# RainbowClock.net
KiCad netlist of a schematic drawn in Altium Designer
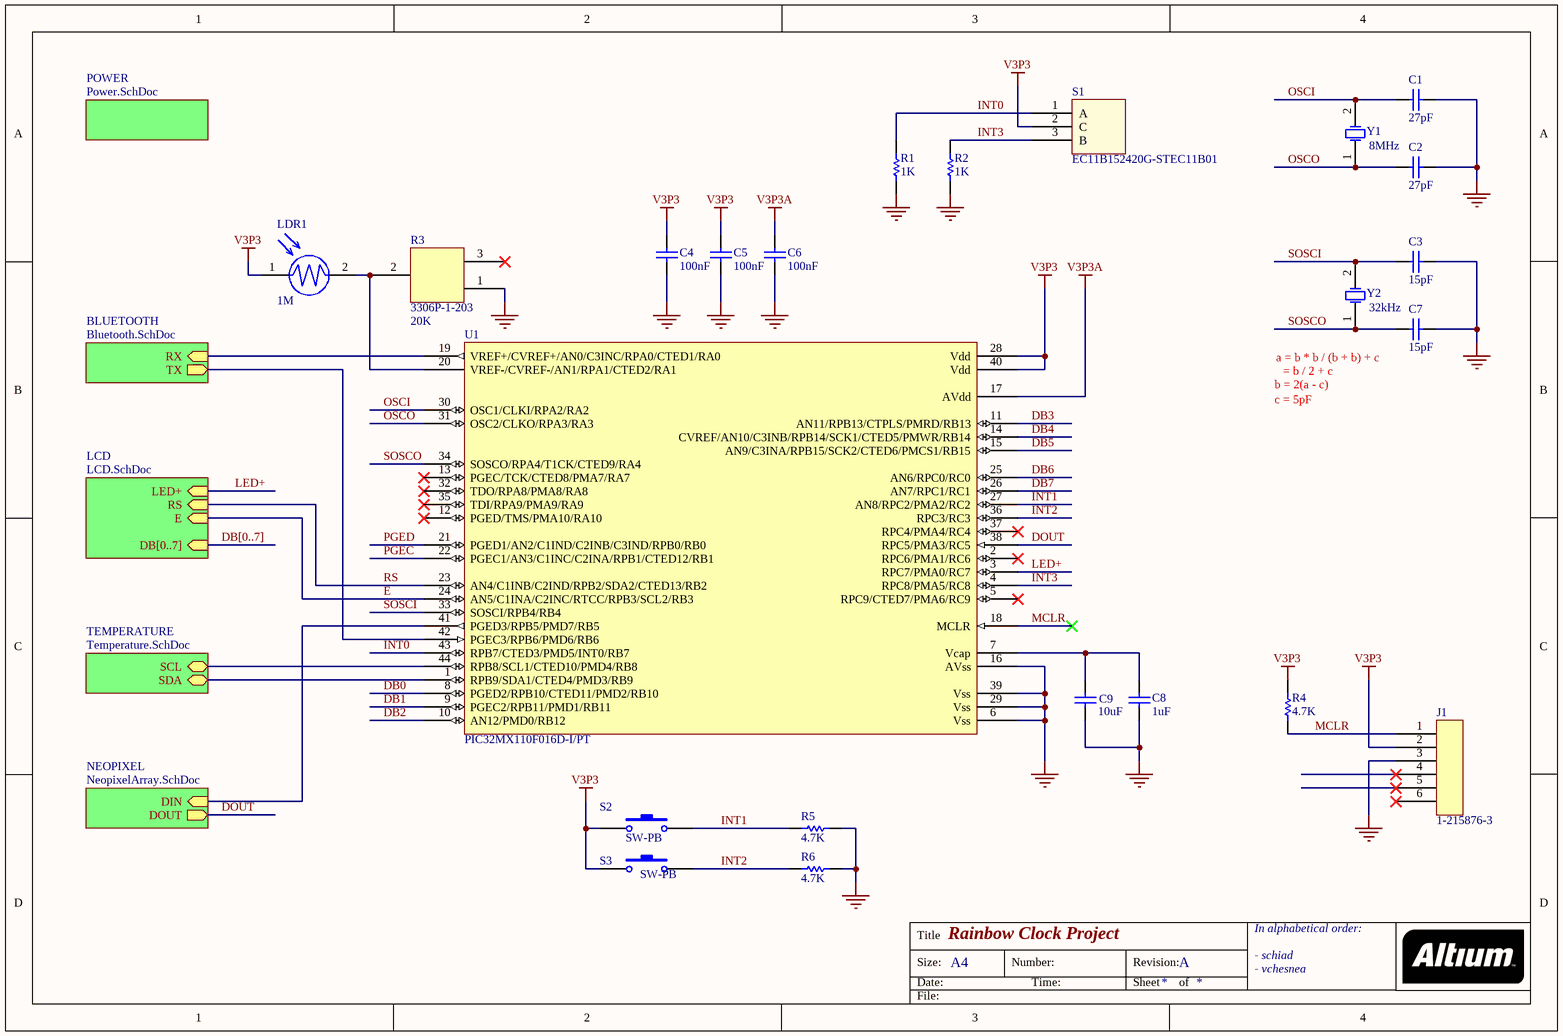
[diagram p0: RainbowClock.SchDoc]

(export (version "E")
  (design (tool "Eeschema 10.0.6"))
  (components
    (comp (ref "C1")
      (value "27pF")
      (footprint "CAP0603")
      (description "Capacitor")
      (libsource (lib "Miscellaneous Devices") (part "Cap"))
    )
    (comp (ref "C2")
      (value "27pF")
      (footprint "CAP0603")
      (description "Capacitor")
      (libsource (lib "Miscellaneous Devices") (part "Cap"))
    )
    (comp (ref "C3")
      (value "15pF")
      (footprint "CAP0603")
      (description "Capacitor")
      (libsource (lib "Miscellaneous Devices") (part "Cap"))
    )
    (comp (ref "C4")
      (value "100nF")
      (footprint "CAP0603")
      (description "Capacitor")
      (libsource (lib "Miscellaneous Devices") (part "Cap"))
    )
    (comp (ref "C5")
      (value "100nF")
      (footprint "CAP0603")
      (description "Capacitor")
      (libsource (lib "Miscellaneous Devices") (part "Cap"))
    )
    (comp (ref "C6")
      (value "100nF")
      (footprint "CAP0603")
      (description "Capacitor")
      (libsource (lib "Miscellaneous Devices") (part "Cap"))
    )
    (comp (ref "C7")
      (value "15pF")
      (footprint "CAP0603")
      (description "Capacitor")
      (libsource (lib "Miscellaneous Devices") (part "Cap"))
    )
    (comp (ref "C8")
      (value "1uF")
      (footprint "CAP0603")
      (description "Capacitor")
      (libsource (lib "Miscellaneous Devices") (part "Cap"))
    )
    (comp (ref "C9")
      (value "10uF")
      (footprint "CAP0603")
      (description "Capacitor")
      (libsource (lib "Miscellaneous Devices") (part "Cap"))
    )
    (comp (ref "J1")
      (value "1-215876-3")
      (description "Tyco 1-215876-3")
      (libsource (lib "Components") (part "1-215876-3"))
    )
    (comp (ref "LDR1")
      (value "1M")
      (footprint "VT935G")
      (description "Photoresistor")
      (fields (field (name "Comment") "LDR"))
      (libsource (lib "Components") (part "LDR"))
    )
    (comp (ref "R1")
      (value "1K")
      (footprint "RES0603")
      (description "Resistor")
      (libsource (lib "Miscellaneous Devices") (part "Res1"))
    )
    (comp (ref "R2")
      (value "1K")
      (footprint "RES0603")
      (description "Resistor")
      (libsource (lib "Miscellaneous Devices") (part "Res1"))
    )
    (comp (ref "R3")
      (value "3306P-1-203")
      (footprint "3306P-1-202")
      (description "Trimpot")
      (fields (field (name "ALTIUM_VALUE") "20K"))
      (libsource (lib "Components") (part "3306P-1-202"))
    )
    (comp (ref "R4")
      (value "4.7K")
      (footprint "RES0603")
      (description "Resistor")
      (libsource (lib "Miscellaneous Devices") (part "Res1"))
    )
    (comp (ref "R5")
      (value "4.7K")
      (footprint "RES0603")
      (description "Resistor")
      (libsource (lib "Miscellaneous Devices") (part "Res1"))
    )
    (comp (ref "R6")
      (value "4.7K")
      (footprint "RES0603")
      (description "Resistor")
      (libsource (lib "Miscellaneous Devices") (part "Res1"))
    )
    (comp (ref "S1")
      (value "EC11B152420G-STEC11B01")
      (footprint "EC11B152420G-STEC11B01")
      (description "Rotary encoder")
      (libsource (lib "Components") (part "EC11B152420G-STEC11B01"))
    )
    (comp (ref "S2")
      (value "SW-PB")
      (footprint "1-1825027-4")
      (description "Switch")
      (libsource (lib "Miscellaneous Devices") (part "SW-PB"))
    )
    (comp (ref "S3")
      (value "SW-PB")
      (footprint "1-1825027-4")
      (description "Switch")
      (libsource (lib "Miscellaneous Devices") (part "SW-PB"))
    )
    (comp (ref "U1")
      (value "PIC32MX110F016D-I/PT")
      (footprint "PIC32MX110F016H-I/PT")
      (description "Microcontroller")
      (libsource (lib "Components") (part "PIC32MX110F016D-I/PT"))
    )
    (comp (ref "Y1")
      (value "8MHz")
      (footprint "FOXSLF/080-20")
      (description "Crystal Oscillator")
      (fields (field (name "Comment") "8MHz XTAL"))
      (libsource (lib "Miscellaneous Devices") (part "XTAL"))
    )
    (comp (ref "Y2")
      (value "32kHz")
      (footprint "NCL38LF")
      (description "Crystal Oscillator")
      (fields (field (name "Comment") "32kHz XTAL"))
      (libsource (lib "Miscellaneous Devices") (part "XTAL"))
    )
  )
  (nets
    (net (code "1") (name "/DB0") (class "Default")
      (node (ref "U1") (pin "8") (pinfunction "PGED2/RPB10/CTED11/PMD2/RB10_8") (pintype "bidirectional"))
    )
    (net (code "2") (name "/DB1") (class "Default")
      (node (ref "U1") (pin "9") (pinfunction "PGEC2/RPB11/PMD1/RB11_9") (pintype "bidirectional"))
    )
    (net (code "3") (name "/DB2") (class "Default")
      (node (ref "U1") (pin "10") (pinfunction "AN12/PMD0/RB12_10") (pintype "bidirectional"))
    )
    (net (code "4") (name "/DB3") (class "Default")
      (node (ref "U1") (pin "11") (pinfunction "AN11/RPB13/CTPLS/PMRD/RB13_11") (pintype "bidirectional"))
    )
    (net (code "5") (name "/DB4") (class "Default")
      (node (ref "U1") (pin "14") (pinfunction "CVREF/AN10/C3INB/RPB14/SCK1/CTED5/PMWR/RB14_14") (pintype "bidirectional"))
    )
    (net (code "6") (name "/DB5") (class "Default")
      (node (ref "U1") (pin "15") (pinfunction "AN9/C3INA/RPB15/SCK2/CTED6/PMCS1/RB15_15") (pintype "bidirectional"))
    )
    (net (code "7") (name "/DB6") (class "Default")
      (node (ref "U1") (pin "25") (pinfunction "AN6/RPC0/RC0_25") (pintype "bidirectional"))
    )
    (net (code "8") (name "/DB7") (class "Default")
      (node (ref "U1") (pin "26") (pinfunction "AN7/RPC1/RC1_26") (pintype "bidirectional"))
    )
    (net (code "10") (name "/DIN") (class "Default")
      (node (ref "U1") (pin "41") (pinfunction "PGED3/RPB5/PMD7/RB5_41") (pintype "output"))
    )
    (net (code "11") (name "/DOUT") (class "Default")
      (node (ref "U1") (pin "38") (pinfunction "RPC5/PMA3/RC5_38") (pintype "input"))
    )
    (net (code "12") (name "/E") (class "Default")
      (node (ref "U1") (pin "24") (pinfunction "AN5/C1INA/C2INC/RTCC/RPB3/SCL2/RB3_24") (pintype "bidirectional"))
    )
    (net (code "13") (name "/INT0") (class "Default")
      (node (ref "R1") (pin "1") (pinfunction "1_1") (pintype "passive"))
      (node (ref "S1") (pin "1") (pinfunction "A_1") (pintype "passive"))
      (node (ref "U1") (pin "43") (pinfunction "RPB7/CTED3/PMD5/INT0/RB7_43") (pintype "bidirectional"))
    )
    (net (code "14") (name "/INT1") (class "Default")
      (node (ref "R5") (pin "2") (pinfunction "2_2") (pintype "passive"))
      (node (ref "S2") (pin "2") (pinfunction "2_2") (pintype "passive"))
      (node (ref "U1") (pin "27") (pinfunction "AN8/RPC2/PMA2/RC2_27") (pintype "bidirectional"))
    )
    (net (code "15") (name "/INT2") (class "Default")
      (node (ref "R6") (pin "2") (pinfunction "2_2") (pintype "passive"))
      (node (ref "S3") (pin "2") (pinfunction "2_2") (pintype "passive"))
      (node (ref "U1") (pin "36") (pinfunction "RPC3/RC3_36") (pintype "bidirectional"))
    )
    (net (code "16") (name "/INT3") (class "Default")
      (node (ref "R2") (pin "2") (pinfunction "2_2") (pintype "passive"))
      (node (ref "S1") (pin "3") (pinfunction "B_3") (pintype "passive"))
      (node (ref "U1") (pin "4") (pinfunction "RPC8/PMA5/RC8_4") (pintype "bidirectional"))
    )
    (net (code "17") (name "/LED+") (class "Default")
      (node (ref "U1") (pin "3") (pinfunction "RPC7/PMA0/RC7_3") (pintype "bidirectional"))
    )
    (net (code "18") (name "/MCLR") (class "Default")
      (node (ref "J1") (pin "1") (pintype "passive"))
      (node (ref "R4") (pin "1") (pinfunction "1_1") (pintype "passive"))
      (node (ref "U1") (pin "18") (pinfunction "MCLR_18") (pintype "input"))
    )
    (net (code "19") (name "/OSCI") (class "Default")
      (node (ref "C1") (pin "1") (pinfunction "1_1") (pintype "passive"))
      (node (ref "U1") (pin "30") (pinfunction "OSC1/CLKI/RPA2/RA2_30") (pintype "bidirectional"))
      (node (ref "Y1") (pin "2") (pinfunction "OSC2_2") (pintype "passive"))
    )
    (net (code "20") (name "/OSCO") (class "Default")
      (node (ref "C2") (pin "1") (pinfunction "1_1") (pintype "passive"))
      (node (ref "U1") (pin "31") (pinfunction "OSC2/CLKO/RPA3/RA3_31") (pintype "bidirectional"))
      (node (ref "Y1") (pin "1") (pinfunction "OSC1_1") (pintype "passive"))
    )
    (net (code "21") (name "/PGEC") (class "Default")
      (node (ref "U1") (pin "22") (pinfunction "PGEC1/AN3/C1INC/C2INA/RPB1/CTED12/RB1_22") (pintype "bidirectional"))
    )
    (net (code "22") (name "/PGED") (class "Default")
      (node (ref "U1") (pin "21") (pinfunction "PGED1/AN2/C1IND/C2INB/C3IND/RPB0/RB0_21") (pintype "bidirectional"))
    )
    (net (code "23") (name "/RS") (class "Default")
      (node (ref "U1") (pin "23") (pinfunction "AN4/C1INB/C2IND/RPB2/SDA2/CTED13/RB2_23") (pintype "bidirectional"))
    )
    (net (code "24") (name "/RX") (class "Default")
      (node (ref "U1") (pin "19") (pinfunction "VREF+/CVREF+/AN0/C3INC/RPA0/CTED1/RA0_19") (pintype "output"))
    )
    (net (code "25") (name "/SCL") (class "Default")
      (node (ref "U1") (pin "44") (pinfunction "RPB8/SCL1/CTED10/PMD4/RB8_44") (pintype "bidirectional"))
    )
    (net (code "26") (name "/SDA") (class "Default")
      (node (ref "U1") (pin "1") (pinfunction "RPB9/SDA1/CTED4/PMD3/RB9_1") (pintype "bidirectional"))
    )
    (net (code "27") (name "/SOSCI") (class "Default")
      (node (ref "C3") (pin "1") (pinfunction "1_1") (pintype "passive"))
      (node (ref "U1") (pin "33") (pinfunction "SOSCI/RPB4/RB4_33") (pintype "bidirectional"))
      (node (ref "Y2") (pin "2") (pinfunction "OSC2_2") (pintype "passive"))
    )
    (net (code "28") (name "/SOSCO") (class "Default")
      (node (ref "C7") (pin "1") (pinfunction "1_1") (pintype "passive"))
      (node (ref "U1") (pin "34") (pinfunction "SOSCO/RPA4/T1CK/CTED9/RA4_34") (pintype "bidirectional"))
      (node (ref "Y2") (pin "1") (pinfunction "OSC1_1") (pintype "passive"))
    )
    (net (code "29") (name "/TX") (class "Default")
      (node (ref "U1") (pin "42") (pinfunction "PGEC3/RPB6/PMD6/RB6_42") (pintype "input"))
    )
    (net (code "30") (name "GND") (class "Default")
      (node (ref "C1") (pin "2") (pinfunction "2_2") (pintype "passive"))
      (node (ref "C2") (pin "2") (pinfunction "2_2") (pintype "passive"))
      (node (ref "C3") (pin "2") (pinfunction "2_2") (pintype "passive"))
      (node (ref "C4") (pin "1") (pinfunction "1_1") (pintype "passive"))
      (node (ref "C5") (pin "1") (pinfunction "1_1") (pintype "passive"))
      (node (ref "C6") (pin "1") (pinfunction "1_1") (pintype "passive"))
      (node (ref "C7") (pin "2") (pinfunction "2_2") (pintype "passive"))
      (node (ref "J1") (pin "3") (pintype "passive"))
      (node (ref "R1") (pin "2") (pinfunction "2_2") (pintype "passive"))
      (node (ref "R2") (pin "1") (pinfunction "1_1") (pintype "passive"))
      (node (ref "R3") (pin "1") (pinfunction "1_1") (pintype "power_in"))
      (node (ref "R5") (pin "1") (pinfunction "1_1") (pintype "passive"))
      (node (ref "R6") (pin "1") (pinfunction "1_1") (pintype "passive"))
    )
    (net (code "31") (name "Net-(U1-VREF-{slash}CVREF-{slash}AN1{slash}RPA1{slash}CTED2{slash}RA1)") (class "Default")
      (node (ref "LDR1") (pin "2") (pinfunction "2_2") (pintype "power_in"))
      (node (ref "R3") (pin "2") (pinfunction "2_2") (pintype "power_in"))
      (node (ref "U1") (pin "20") (pinfunction "VREF-/CVREF-/AN1/RPA1/CTED2/RA1_20") (pintype "passive"))
    )
    (net (code "32") (name "Net-(U1-Vcap)") (class "Default")
      (node (ref "C8") (pin "2") (pinfunction "2_2") (pintype "passive"))
      (node (ref "C9") (pin "2") (pinfunction "2_2") (pintype "passive"))
      (node (ref "U1") (pin "7") (pinfunction "Vcap_7") (pintype "power_in"))
    )
    (net (code "33") (name "V3P3") (class "Default")
      (node (ref "C4") (pin "2") (pinfunction "2_2") (pintype "passive"))
      (node (ref "C5") (pin "2") (pinfunction "2_2") (pintype "passive"))
      (node (ref "J1") (pin "2") (pintype "passive"))
      (node (ref "LDR1") (pin "1") (pinfunction "1_1") (pintype "power_in"))
      (node (ref "R4") (pin "2") (pinfunction "2_2") (pintype "passive"))
      (node (ref "S1") (pin "2") (pinfunction "C_2") (pintype "passive"))
      (node (ref "S2") (pin "1") (pinfunction "1_1") (pintype "passive"))
      (node (ref "S3") (pin "1") (pinfunction "1_1") (pintype "passive"))
      (node (ref "U1") (pin "28") (pinfunction "Vdd_28") (pintype "power_in"))
      (node (ref "U1") (pin "40") (pinfunction "Vdd_40") (pintype "power_in"))
    )
    (net (code "34") (name "V3P3A") (class "Default")
      (node (ref "C6") (pin "2") (pinfunction "2_2") (pintype "passive"))
      (node (ref "U1") (pin "17") (pinfunction "AVdd_17") (pintype "power_in"))
    )
    (net (code "35") (name "VSS") (class "Default")
      (node (ref "C8") (pin "1") (pinfunction "1_1") (pintype "passive"))
      (node (ref "C9") (pin "1") (pinfunction "1_1") (pintype "passive"))
      (node (ref "U1") (pin "16") (pinfunction "AVss_16") (pintype "power_in"))
      (node (ref "U1") (pin "29") (pinfunction "Vss_29") (pintype "power_in"))
      (node (ref "U1") (pin "39") (pinfunction "Vss_39") (pintype "power_in"))
      (node (ref "U1") (pin "6") (pinfunction "Vss_6") (pintype "power_in"))
    )
    (net (code "36") (name "unconnected-(J1-Pad4)") (class "Default")
      (node (ref "J1") (pin "4") (pintype "passive+no_connect"))
    )
    (net (code "37") (name "unconnected-(J1-Pad5)") (class "Default")
      (node (ref "J1") (pin "5") (pintype "passive+no_connect"))
    )
    (net (code "38") (name "unconnected-(J1-Pad6)") (class "Default")
      (node (ref "J1") (pin "6") (pintype "passive+no_connect"))
    )
    (net (code "39") (name "unconnected-(R3-Pad3)") (class "Default")
      (node (ref "R3") (pin "3") (pinfunction "3_3") (pintype "power_in+no_connect"))
    )
    (net (code "40") (name "unconnected-(U1-PGEC{slash}TCK{slash}CTED8{slash}PMA7{slash}RA7-Pad13)") (class "Default")
      (node (ref "U1") (pin "13") (pinfunction "PGEC/TCK/CTED8/PMA7/RA7_13") (pintype "bidirectional+no_connect"))
    )
    (net (code "41") (name "unconnected-(U1-PGED{slash}TMS{slash}PMA10{slash}RA10-Pad12)") (class "Default")
      (node (ref "U1") (pin "12") (pinfunction "PGED/TMS/PMA10/RA10_12") (pintype "bidirectional+no_connect"))
    )
    (net (code "42") (name "unconnected-(U1-RPC4{slash}PMA4{slash}RC4-Pad37)") (class "Default")
      (node (ref "U1") (pin "37") (pinfunction "RPC4/PMA4/RC4_37") (pintype "bidirectional+no_connect"))
    )
    (net (code "43") (name "unconnected-(U1-RPC6{slash}PMA1{slash}RC6-Pad2)") (class "Default")
      (node (ref "U1") (pin "2") (pinfunction "RPC6/PMA1/RC6_2") (pintype "bidirectional+no_connect"))
    )
    (net (code "44") (name "unconnected-(U1-RPC9{slash}CTED7{slash}PMA6{slash}RC9-Pad5)") (class "Default")
      (node (ref "U1") (pin "5") (pinfunction "RPC9/CTED7/PMA6/RC9_5") (pintype "bidirectional+no_connect"))
    )
    (net (code "45") (name "unconnected-(U1-TDI{slash}RPA9{slash}PMA9{slash}RA9-Pad35)") (class "Default")
      (node (ref "U1") (pin "35") (pinfunction "TDI/RPA9/PMA9/RA9_35") (pintype "bidirectional+no_connect"))
    )
    (net (code "46") (name "unconnected-(U1-TDO{slash}RPA8{slash}PMA8{slash}RA8-Pad32)") (class "Default")
      (node (ref "U1") (pin "32") (pinfunction "TDO/RPA8/PMA8/RA8_32") (pintype "bidirectional+no_connect"))
    )
  )
)
